# KEY_PCB.net
KiCad netlist of a schematic drawn in Altium Designer
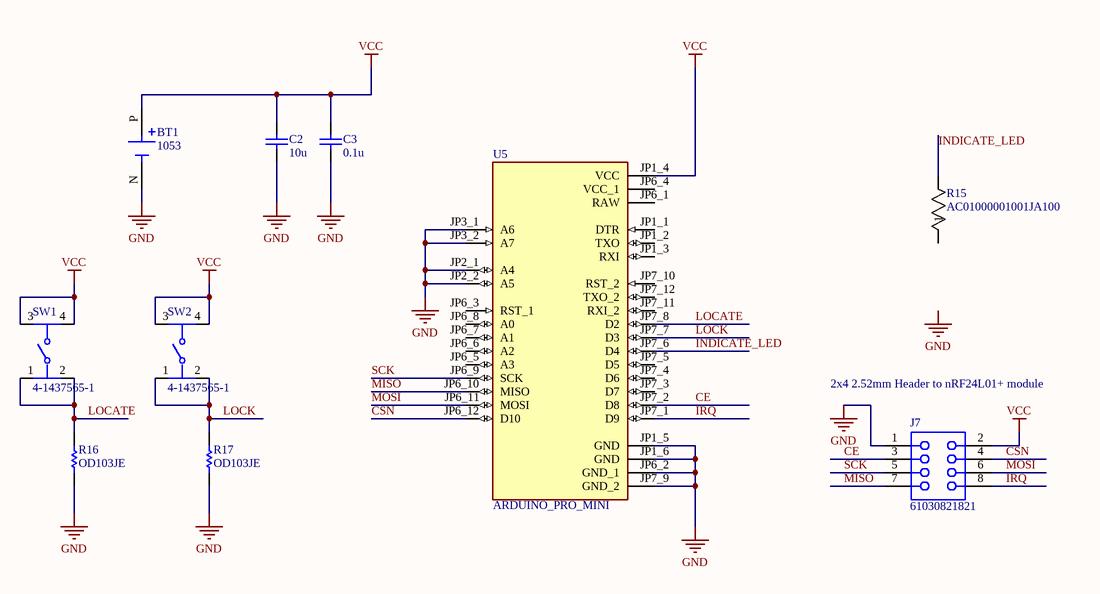
[diagram p0: KEY_PCB.SchDoc]

(export (version "E")
  (design (tool "Eeschema 10.0.6"))
  (components
    (comp (ref "BT1")
      (value "1053")
      (footprint "BAT_1053")
      (fields (field (name "MF") "Keystone Electronics"))
      (libsource (lib "1053") (part "1053"))
    )
    (comp (ref "C2")
      (value "10u")
      (description "Capacitor")
      (libsource (lib "Simulation Generic Components") (part "Capacitor"))
    )
    (comp (ref "C3")
      (value "0.1u")
      (description "Capacitor")
      (libsource (lib "Simulation Generic Components") (part "Capacitor"))
    )
    (comp (ref "J7")
      (value "61030821821")
      (footprint "61030821821")
      (libsource (lib "Altium Content Vault") (part "Header_Female_2R_08P"))
    )
    (comp (ref "R15")
      (value "AC01000001001JA100")
      (footprint "RES_AC01_VIS")
      (description "VISHAY AC01000001001JA100 Through Hole Resistor, 1 kohm, Axial Leaded, 1 W, 5%, AC Series")
      (fields (field (name "TOLERANCE") "5%"))
      (libsource (lib "Altium Content Vault") (part "AC01000001001JA100"))
    )
    (comp (ref "R16")
      (value "OD103JE")
      (footprint "OMTE-RES7X2.5-2")
      (fields (field (name "TOLERANCE") "±5%") (field (name "MANUFACTURER") "Ohmite"))
      (libsource (lib "Altium Content Vault") (part "RES-2"))
    )
    (comp (ref "R17")
      (value "OD103JE")
      (footprint "OMTE-RES7X2.5-2")
      (fields (field (name "TOLERANCE") "±5%") (field (name "MANUFACTURER") "Ohmite"))
      (libsource (lib "Altium Content Vault") (part "RES-2"))
    )
    (comp (ref "SW1")
      (value "4-1437565-1")
      (footprint "FP-4-1437565-1-MFG")
      (description "SWITCH TACTILE SPST-NO 0.05A 24V")
      (fields
        (field (name "MANUFACTURER") "TE Connectivity")
        (field (name "OCTOPART") "https://octopart.com/fsm4jsma-te+connectivity-55488004")
      )
      (libsource (lib "Altium Content Vault") (part "b8895f3f4cefb76e1819d2863dba89b"))
    )
    (comp (ref "SW2")
      (value "4-1437565-1")
      (footprint "FP-4-1437565-1-MFG")
      (description "SWITCH TACTILE SPST-NO 0.05A 24V")
      (fields
        (field (name "MANUFACTURER") "TE Connectivity")
        (field (name "OCTOPART") "https://octopart.com/fsm4jsma-te+connectivity-55488004")
      )
      (libsource (lib "Altium Content Vault") (part "b8895f3f4cefb76e1819d2863dba89b"))
    )
    (comp (ref "U5")
      (value "ARDUINO_PRO_MINI")
      (footprint "MODULE_ARDUINO_PRO_MINI")
      (fields (field (name "MF") "Arduino") (field (name "MP") "Arduino Pro Mini"))
      (libsource (lib "ARDUINO_PRO_MINI") (part "ARDUINO_PRO_MINI"))
    )
  )
  (nets
    (net (code "1") (name "/CE") (class "Default")
      (node (ref "J7") (pin "3") (pinfunction "3_3") (pintype "passive"))
      (node (ref "U5") (pin "JP7_2") (pinfunction "D8_JP7_2") (pintype "bidirectional"))
    )
    (net (code "2") (name "/CSN") (class "Default")
      (node (ref "J7") (pin "4") (pinfunction "4_4") (pintype "passive"))
      (node (ref "U5") (pin "JP6_12") (pinfunction "D10_JP6_12") (pintype "bidirectional"))
    )
    (net (code "3") (name "/INDICATE_LED") (class "Default")
      (node (ref "R15") (pin "2") (pinfunction "2_2") (pintype "passive"))
      (node (ref "U5") (pin "JP7_6") (pinfunction "D4_JP7_6") (pintype "bidirectional"))
    )
    (net (code "4") (name "/IRQ") (class "Default")
      (node (ref "J7") (pin "8") (pinfunction "8_8") (pintype "passive"))
      (node (ref "U5") (pin "JP7_1") (pinfunction "D9_JP7_1") (pintype "bidirectional"))
    )
    (net (code "5") (name "/LOCATE") (class "Default")
      (node (ref "R16") (pin "2") (pinfunction "2_2") (pintype "passive"))
      (node (ref "SW1") (pin "1") (pinfunction "1_1") (pintype "passive"))
      (node (ref "SW1") (pin "2") (pinfunction "2_2") (pintype "passive"))
      (node (ref "U5") (pin "JP7_8") (pinfunction "D2_JP7_8") (pintype "bidirectional"))
    )
    (net (code "6") (name "/LOCK") (class "Default")
      (node (ref "R17") (pin "2") (pinfunction "2_2") (pintype "passive"))
      (node (ref "SW2") (pin "1") (pinfunction "1_1") (pintype "passive"))
      (node (ref "SW2") (pin "2") (pinfunction "2_2") (pintype "passive"))
      (node (ref "U5") (pin "JP7_7") (pinfunction "D3_JP7_7") (pintype "bidirectional"))
    )
    (net (code "7") (name "/MISO") (class "Default")
      (node (ref "J7") (pin "7") (pinfunction "7_7") (pintype "passive"))
      (node (ref "U5") (pin "JP6_10") (pinfunction "MISO_JP6_10") (pintype "bidirectional"))
    )
    (net (code "8") (name "/MOSI") (class "Default")
      (node (ref "J7") (pin "6") (pinfunction "6_6") (pintype "passive"))
      (node (ref "U5") (pin "JP6_11") (pinfunction "MOSI_JP6_11") (pintype "bidirectional"))
    )
    (net (code "9") (name "/SCK") (class "Default")
      (node (ref "J7") (pin "5") (pinfunction "5_5") (pintype "passive"))
      (node (ref "U5") (pin "JP6_9") (pinfunction "SCK_JP6_9") (pintype "bidirectional"))
    )
    (net (code "10") (name "GND") (class "Default")
      (node (ref "BT1") (pin "N") (pinfunction "NEG_N") (pintype "passive"))
      (node (ref "C2") (pin "1") (pinfunction "1_1") (pintype "passive"))
      (node (ref "C3") (pin "1") (pinfunction "1_1") (pintype "passive"))
      (node (ref "J7") (pin "1") (pinfunction "1_1") (pintype "passive"))
      (node (ref "R16") (pin "1") (pinfunction "1_1") (pintype "passive"))
      (node (ref "R17") (pin "1") (pinfunction "1_1") (pintype "passive"))
      (node (ref "U5") (pin "JP1_5") (pinfunction "GND_JP1_5") (pintype "power_in"))
      (node (ref "U5") (pin "JP1_6") (pinfunction "GND_JP1_6") (pintype "power_in"))
      (node (ref "U5") (pin "JP2_1") (pinfunction "A4_JP2_1") (pintype "bidirectional"))
      (node (ref "U5") (pin "JP2_2") (pinfunction "A5_JP2_2") (pintype "bidirectional"))
      (node (ref "U5") (pin "JP3_1") (pinfunction "A6_JP3_1") (pintype "input"))
      (node (ref "U5") (pin "JP3_2") (pinfunction "A7_JP3_2") (pintype "input"))
      (node (ref "U5") (pin "JP6_2") (pinfunction "GND_1_JP6_2") (pintype "power_in"))
      (node (ref "U5") (pin "JP7_9") (pinfunction "GND_2_JP7_9") (pintype "power_in"))
    )
    (net (code "11") (name "VCC") (class "Default")
      (node (ref "BT1") (pin "P") (pinfunction "POS_P") (pintype "passive"))
      (node (ref "C2") (pin "2") (pinfunction "2_2") (pintype "passive"))
      (node (ref "C3") (pin "2") (pinfunction "2_2") (pintype "passive"))
      (node (ref "J7") (pin "2") (pinfunction "2_2") (pintype "passive"))
      (node (ref "SW1") (pin "3") (pinfunction "3_3") (pintype "passive"))
      (node (ref "SW1") (pin "4") (pinfunction "4_4") (pintype "passive"))
      (node (ref "SW2") (pin "3") (pinfunction "3_3") (pintype "passive"))
      (node (ref "SW2") (pin "4") (pinfunction "4_4") (pintype "passive"))
      (node (ref "U5") (pin "JP1_4") (pinfunction "VCC_JP1_4") (pintype "power_in"))
    )
    (net (code "12") (name "unconnected-(R15-Pad1)") (class "Default")
      (node (ref "R15") (pin "1") (pinfunction "1_1") (pintype "passive"))
    )
    (net (code "13") (name "unconnected-(U5-A0-PadJP6_8)") (class "Default")
      (node (ref "U5") (pin "JP6_8") (pinfunction "A0_JP6_8") (pintype "bidirectional"))
    )
    (net (code "14") (name "unconnected-(U5-A1-PadJP6_7)") (class "Default")
      (node (ref "U5") (pin "JP6_7") (pinfunction "A1_JP6_7") (pintype "bidirectional"))
    )
    (net (code "15") (name "unconnected-(U5-A2-PadJP6_6)") (class "Default")
      (node (ref "U5") (pin "JP6_6") (pinfunction "A2_JP6_6") (pintype "bidirectional"))
    )
    (net (code "16") (name "unconnected-(U5-A3-PadJP6_5)") (class "Default")
      (node (ref "U5") (pin "JP6_5") (pinfunction "A3_JP6_5") (pintype "bidirectional"))
    )
    (net (code "17") (name "unconnected-(U5-D5-PadJP7_5)") (class "Default")
      (node (ref "U5") (pin "JP7_5") (pinfunction "D5_JP7_5") (pintype "bidirectional"))
    )
    (net (code "18") (name "unconnected-(U5-D6-PadJP7_4)") (class "Default")
      (node (ref "U5") (pin "JP7_4") (pinfunction "D6_JP7_4") (pintype "bidirectional"))
    )
    (net (code "19") (name "unconnected-(U5-D7-PadJP7_3)") (class "Default")
      (node (ref "U5") (pin "JP7_3") (pinfunction "D7_JP7_3") (pintype "bidirectional"))
    )
    (net (code "20") (name "unconnected-(U5-DTR-PadJP1_1)") (class "Default")
      (node (ref "U5") (pin "JP1_1") (pinfunction "DTR_JP1_1") (pintype "input"))
    )
    (net (code "21") (name "unconnected-(U5-RAW-PadJP6_1)") (class "Default")
      (node (ref "U5") (pin "JP6_1") (pinfunction "RAW_JP6_1") (pintype "power_in"))
    )
    (net (code "22") (name "unconnected-(U5-RST_1-PadJP6_3)") (class "Default")
      (node (ref "U5") (pin "JP6_3") (pinfunction "RST_1_JP6_3") (pintype "input"))
    )
    (net (code "23") (name "unconnected-(U5-RST_2-PadJP7_10)") (class "Default")
      (node (ref "U5") (pin "JP7_10") (pinfunction "RST_2_JP7_10") (pintype "input"))
    )
    (net (code "24") (name "unconnected-(U5-RXI-PadJP1_3)") (class "Default")
      (node (ref "U5") (pin "JP1_3") (pinfunction "RXI_JP1_3") (pintype "bidirectional"))
    )
    (net (code "25") (name "unconnected-(U5-RXI_2-PadJP7_11)") (class "Default")
      (node (ref "U5") (pin "JP7_11") (pinfunction "RXI_2_JP7_11") (pintype "bidirectional"))
    )
    (net (code "26") (name "unconnected-(U5-TXO-PadJP1_2)") (class "Default")
      (node (ref "U5") (pin "JP1_2") (pinfunction "TXO_JP1_2") (pintype "bidirectional"))
    )
    (net (code "27") (name "unconnected-(U5-TXO_2-PadJP7_12)") (class "Default")
      (node (ref "U5") (pin "JP7_12") (pinfunction "TXO_2_JP7_12") (pintype "bidirectional"))
    )
    (net (code "28") (name "unconnected-(U5-VCC_1-PadJP6_4)") (class "Default")
      (node (ref "U5") (pin "JP6_4") (pinfunction "VCC_1_JP6_4") (pintype "power_in"))
    )
  )
)
